# comm-board.net
KiCad netlist of a schematic drawn in EAGLE
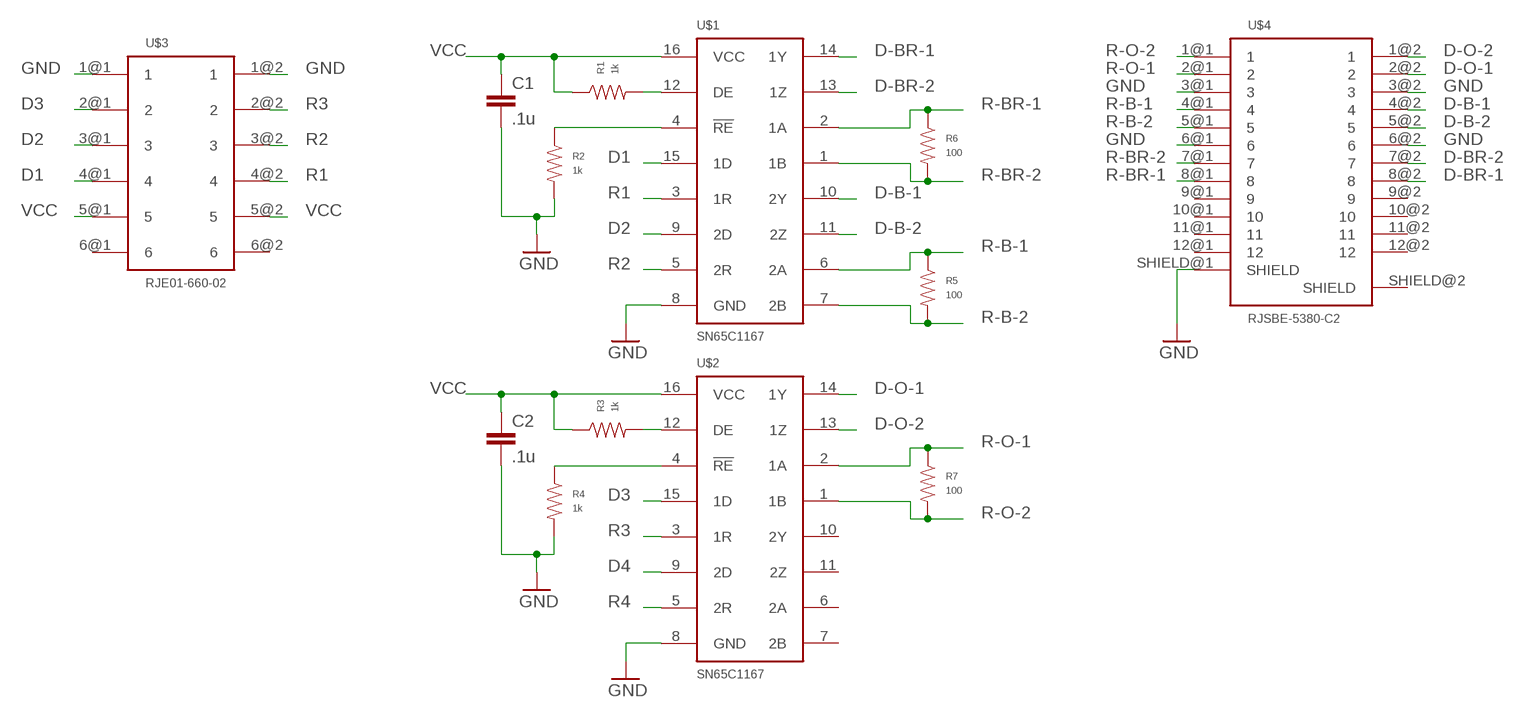
[diagram p0: schematic, sheet 1]

(export (version "E")
  (design (tool "Eeschema 10.0.6"))
  (components
    (comp (ref "C1")
      (value ".1u")
      (footprint "eagle-import:0805")
      (libsource (lib "eagle-import") (part "CAP0805"))
    )
    (comp (ref "C2")
      (value ".1u")
      (footprint "eagle-import:0805")
      (libsource (lib "eagle-import") (part "CAP0805"))
    )
    (comp (ref "R1")
      (value "1k")
      (footprint "eagle-import:R0805")
      (libsource (lib "eagle-import") (part "RESISTOR_0805"))
    )
    (comp (ref "R2")
      (value "1k")
      (footprint "eagle-import:R0805")
      (libsource (lib "eagle-import") (part "RESISTOR_0805"))
    )
    (comp (ref "R3")
      (value "1k")
      (footprint "eagle-import:R0805")
      (libsource (lib "eagle-import") (part "RESISTOR_0805"))
    )
    (comp (ref "R4")
      (value "1k")
      (footprint "eagle-import:R0805")
      (libsource (lib "eagle-import") (part "RESISTOR_0805"))
    )
    (comp (ref "R5")
      (value "100")
      (footprint "eagle-import:R0805")
      (libsource (lib "eagle-import") (part "RESISTOR_0805"))
    )
    (comp (ref "R6")
      (value "100")
      (footprint "eagle-import:R0805")
      (libsource (lib "eagle-import") (part "RESISTOR_0805"))
    )
    (comp (ref "R7")
      (value "100")
      (footprint "eagle-import:R0805")
      (libsource (lib "eagle-import") (part "RESISTOR_0805"))
    )
    (comp (ref "U$1")
      (value "SN65C1167")
      (footprint "eagle-import:SOP-16")
      (libsource (lib "eagle-import") (part "SN65C1167"))
    )
    (comp (ref "U$2")
      (value "SN65C1167")
      (footprint "eagle-import:SOP-16")
      (libsource (lib "eagle-import") (part "SN65C1167"))
    )
    (comp (ref "U$3")
      (value "RJE01-660-02")
      (footprint "eagle-import:RJE01-660-02")
      (libsource (lib "eagle-import") (part "RJE01-660-02"))
    )
    (comp (ref "U$4")
      (value "RJSBE-5380-C2")
      (footprint "eagle-import:RJSBE-5380-C2")
      (libsource (lib "eagle-import") (part "RJSBE-5380-C2"))
    )
  )
  (nets
    (net (code "1") (name "/D-B-1") (class "Default")
      (node (ref "U$1") (pin "10") (pinfunction "2Y_10") (pintype "bidirectional"))
      (node (ref "U$4") (pin "4@2") (pinfunction "4_4@2") (pintype "bidirectional"))
    )
    (net (code "2") (name "/D-B-2") (class "Default")
      (node (ref "U$1") (pin "11") (pinfunction "2Z_11") (pintype "bidirectional"))
      (node (ref "U$4") (pin "5@2") (pinfunction "5_5@2") (pintype "bidirectional"))
    )
    (net (code "3") (name "/D-BR-1") (class "Default")
      (node (ref "U$1") (pin "14") (pinfunction "1Y_14") (pintype "bidirectional"))
      (node (ref "U$4") (pin "8@2") (pinfunction "8_8@2") (pintype "bidirectional"))
    )
    (net (code "4") (name "/D-BR-2") (class "Default")
      (node (ref "U$1") (pin "13") (pinfunction "1Z_13") (pintype "bidirectional"))
      (node (ref "U$4") (pin "7@2") (pinfunction "7_7@2") (pintype "bidirectional"))
    )
    (net (code "5") (name "/D-O-1") (class "Default")
      (node (ref "U$2") (pin "14") (pinfunction "1Y_14") (pintype "bidirectional"))
      (node (ref "U$4") (pin "2@2") (pinfunction "2_2@2") (pintype "bidirectional"))
    )
    (net (code "6") (name "/D-O-2") (class "Default")
      (node (ref "U$2") (pin "13") (pinfunction "1Z_13") (pintype "bidirectional"))
      (node (ref "U$4") (pin "1@2") (pinfunction "1_1@2") (pintype "bidirectional"))
    )
    (net (code "7") (name "/D1") (class "Default")
      (node (ref "U$1") (pin "15") (pinfunction "1D_15") (pintype "bidirectional"))
      (node (ref "U$3") (pin "4@1") (pinfunction "4_4@1") (pintype "bidirectional"))
    )
    (net (code "8") (name "/D2") (class "Default")
      (node (ref "U$1") (pin "9") (pinfunction "2D_9") (pintype "bidirectional"))
      (node (ref "U$3") (pin "3@1") (pinfunction "3_3@1") (pintype "bidirectional"))
    )
    (net (code "9") (name "/D3") (class "Default")
      (node (ref "U$2") (pin "15") (pinfunction "1D_15") (pintype "bidirectional"))
      (node (ref "U$3") (pin "2@1") (pinfunction "2_2@1") (pintype "bidirectional"))
    )
    (net (code "10") (name "/D4") (class "Default")
      (node (ref "U$2") (pin "9") (pinfunction "2D_9") (pintype "bidirectional"))
    )
    (net (code "11") (name "/R-B-1") (class "Default")
      (node (ref "R5") (pin "P$1") (pinfunction "P$1_P$1") (pintype "passive"))
      (node (ref "U$1") (pin "6") (pinfunction "2A_6") (pintype "bidirectional"))
      (node (ref "U$4") (pin "4@1") (pinfunction "4_4@1") (pintype "bidirectional"))
    )
    (net (code "12") (name "/R-B-2") (class "Default")
      (node (ref "R5") (pin "P$2") (pinfunction "P$2_P$2") (pintype "passive"))
      (node (ref "U$1") (pin "7") (pinfunction "2B_7") (pintype "bidirectional"))
      (node (ref "U$4") (pin "5@1") (pinfunction "5_5@1") (pintype "bidirectional"))
    )
    (net (code "13") (name "/R-BR-1") (class "Default")
      (node (ref "R6") (pin "P$1") (pinfunction "P$1_P$1") (pintype "passive"))
      (node (ref "U$1") (pin "2") (pinfunction "1A_2") (pintype "bidirectional"))
      (node (ref "U$4") (pin "8@1") (pinfunction "8_8@1") (pintype "bidirectional"))
    )
    (net (code "14") (name "/R-BR-2") (class "Default")
      (node (ref "R6") (pin "P$2") (pinfunction "P$2_P$2") (pintype "passive"))
      (node (ref "U$1") (pin "1") (pinfunction "1B_1") (pintype "bidirectional"))
      (node (ref "U$4") (pin "7@1") (pinfunction "7_7@1") (pintype "bidirectional"))
    )
    (net (code "15") (name "/R-O-1") (class "Default")
      (node (ref "R7") (pin "P$1") (pinfunction "P$1_P$1") (pintype "passive"))
      (node (ref "U$2") (pin "2") (pinfunction "1A_2") (pintype "bidirectional"))
      (node (ref "U$4") (pin "2@1") (pinfunction "2_2@1") (pintype "bidirectional"))
    )
    (net (code "16") (name "/R-O-2") (class "Default")
      (node (ref "R7") (pin "P$2") (pinfunction "P$2_P$2") (pintype "passive"))
      (node (ref "U$2") (pin "1") (pinfunction "1B_1") (pintype "bidirectional"))
      (node (ref "U$4") (pin "1@1") (pinfunction "1_1@1") (pintype "bidirectional"))
    )
    (net (code "17") (name "/R1") (class "Default")
      (node (ref "U$1") (pin "3") (pinfunction "1R_3") (pintype "bidirectional"))
      (node (ref "U$3") (pin "4@2") (pinfunction "4_4@2") (pintype "bidirectional"))
    )
    (net (code "18") (name "/R2") (class "Default")
      (node (ref "U$1") (pin "5") (pinfunction "2R_5") (pintype "bidirectional"))
      (node (ref "U$3") (pin "3@2") (pinfunction "3_3@2") (pintype "bidirectional"))
    )
    (net (code "19") (name "/R3") (class "Default")
      (node (ref "U$2") (pin "3") (pinfunction "1R_3") (pintype "bidirectional"))
      (node (ref "U$3") (pin "2@2") (pinfunction "2_2@2") (pintype "bidirectional"))
    )
    (net (code "20") (name "/R4") (class "Default")
      (node (ref "U$2") (pin "5") (pinfunction "2R_5") (pintype "bidirectional"))
    )
    (net (code "21") (name "/VCC") (class "Default")
      (node (ref "C1") (pin "1") (pinfunction "1_1") (pintype "passive"))
      (node (ref "C2") (pin "1") (pinfunction "1_1") (pintype "passive"))
      (node (ref "R1") (pin "P$1") (pinfunction "P$1_P$1") (pintype "passive"))
      (node (ref "R3") (pin "P$1") (pinfunction "P$1_P$1") (pintype "passive"))
      (node (ref "U$1") (pin "16") (pinfunction "VCC_16") (pintype "bidirectional"))
      (node (ref "U$2") (pin "16") (pinfunction "VCC_16") (pintype "bidirectional"))
      (node (ref "U$3") (pin "5@1") (pinfunction "5_5@1") (pintype "bidirectional"))
      (node (ref "U$3") (pin "5@2") (pinfunction "5_5@2") (pintype "bidirectional"))
    )
    (net (code "22") (name "GND") (class "Default")
      (node (ref "C1") (pin "2") (pinfunction "2_2") (pintype "passive"))
      (node (ref "C2") (pin "2") (pinfunction "2_2") (pintype "passive"))
      (node (ref "R2") (pin "P$2") (pinfunction "P$2_P$2") (pintype "passive"))
      (node (ref "R4") (pin "P$2") (pinfunction "P$2_P$2") (pintype "passive"))
      (node (ref "U$1") (pin "8") (pinfunction "GND_8") (pintype "bidirectional"))
      (node (ref "U$2") (pin "8") (pinfunction "GND_8") (pintype "bidirectional"))
      (node (ref "U$3") (pin "1@1") (pinfunction "1_1@1") (pintype "bidirectional"))
      (node (ref "U$3") (pin "1@2") (pinfunction "1_1@2") (pintype "bidirectional"))
      (node (ref "U$4") (pin "3@1") (pinfunction "3_3@1") (pintype "bidirectional"))
      (node (ref "U$4") (pin "3@2") (pinfunction "3_3@2") (pintype "bidirectional"))
      (node (ref "U$4") (pin "6@1") (pinfunction "6_6@1") (pintype "bidirectional"))
      (node (ref "U$4") (pin "6@2") (pinfunction "6_6@2") (pintype "bidirectional"))
      (node (ref "U$4") (pin "SHIELD@1") (pinfunction "SHIELD_SHIELD@1") (pintype "bidirectional"))
    )
    (net (code "23") (name "Net-(U$1-DE)") (class "Default")
      (node (ref "R1") (pin "P$2") (pinfunction "P$2_P$2") (pintype "passive"))
      (node (ref "U$1") (pin "12") (pinfunction "DE_12") (pintype "bidirectional"))
    )
    (net (code "24") (name "Net-(U$1-~{RE})") (class "Default")
      (node (ref "R2") (pin "P$1") (pinfunction "P$1_P$1") (pintype "passive"))
      (node (ref "U$1") (pin "4") (pinfunction "~{RE}_4") (pintype "bidirectional"))
    )
    (net (code "25") (name "Net-(U$2-DE)") (class "Default")
      (node (ref "R3") (pin "P$2") (pinfunction "P$2_P$2") (pintype "passive"))
      (node (ref "U$2") (pin "12") (pinfunction "DE_12") (pintype "bidirectional"))
    )
    (net (code "26") (name "Net-(U$2-~{RE})") (class "Default")
      (node (ref "R4") (pin "P$1") (pinfunction "P$1_P$1") (pintype "passive"))
      (node (ref "U$2") (pin "4") (pinfunction "~{RE}_4") (pintype "bidirectional"))
    )
    (net (code "27") (name "unconnected-(U$2-2A-Pad6)") (class "Default")
      (node (ref "U$2") (pin "6") (pinfunction "2A_6") (pintype "bidirectional"))
    )
    (net (code "28") (name "unconnected-(U$2-2B-Pad7)") (class "Default")
      (node (ref "U$2") (pin "7") (pinfunction "2B_7") (pintype "bidirectional"))
    )
    (net (code "29") (name "unconnected-(U$2-2Y-Pad10)") (class "Default")
      (node (ref "U$2") (pin "10") (pinfunction "2Y_10") (pintype "bidirectional"))
    )
    (net (code "30") (name "unconnected-(U$2-2Z-Pad11)") (class "Default")
      (node (ref "U$2") (pin "11") (pinfunction "2Z_11") (pintype "bidirectional"))
    )
    (net (code "31") (name "unconnected-(U$3-6-Pad6@1)") (class "Default")
      (node (ref "U$3") (pin "6@1") (pinfunction "6_6@1") (pintype "bidirectional"))
    )
    (net (code "32") (name "unconnected-(U$3-6-Pad6@2)") (class "Default")
      (node (ref "U$3") (pin "6@2") (pinfunction "6_6@2") (pintype "bidirectional"))
    )
    (net (code "33") (name "unconnected-(U$4-9-Pad9@1)") (class "Default")
      (node (ref "U$4") (pin "9@1") (pinfunction "9_9@1") (pintype "bidirectional"))
    )
    (net (code "34") (name "unconnected-(U$4-9-Pad9@2)") (class "Default")
      (node (ref "U$4") (pin "9@2") (pinfunction "9_9@2") (pintype "bidirectional"))
    )
    (net (code "35") (name "unconnected-(U$4-10-Pad10@1)") (class "Default")
      (node (ref "U$4") (pin "10@1") (pinfunction "10_10@1") (pintype "bidirectional"))
    )
    (net (code "36") (name "unconnected-(U$4-10-Pad10@2)") (class "Default")
      (node (ref "U$4") (pin "10@2") (pinfunction "10_10@2") (pintype "bidirectional"))
    )
    (net (code "37") (name "unconnected-(U$4-11-Pad11@1)") (class "Default")
      (node (ref "U$4") (pin "11@1") (pinfunction "11_11@1") (pintype "bidirectional"))
    )
    (net (code "38") (name "unconnected-(U$4-11-Pad11@2)") (class "Default")
      (node (ref "U$4") (pin "11@2") (pinfunction "11_11@2") (pintype "bidirectional"))
    )
    (net (code "39") (name "unconnected-(U$4-12-Pad12@1)") (class "Default")
      (node (ref "U$4") (pin "12@1") (pinfunction "12_12@1") (pintype "bidirectional"))
    )
    (net (code "40") (name "unconnected-(U$4-12-Pad12@2)") (class "Default")
      (node (ref "U$4") (pin "12@2") (pinfunction "12_12@2") (pintype "bidirectional"))
    )
    (net (code "41") (name "unconnected-(U$4-SHIELD-PadSHIELD@2)") (class "Default")
      (node (ref "U$4") (pin "SHIELD@2") (pinfunction "SHIELD_SHIELD@2") (pintype "bidirectional"))
    )
  )
)
